# vme_conn.net
KiCad netlist of a schematic drawn in Altium Designer
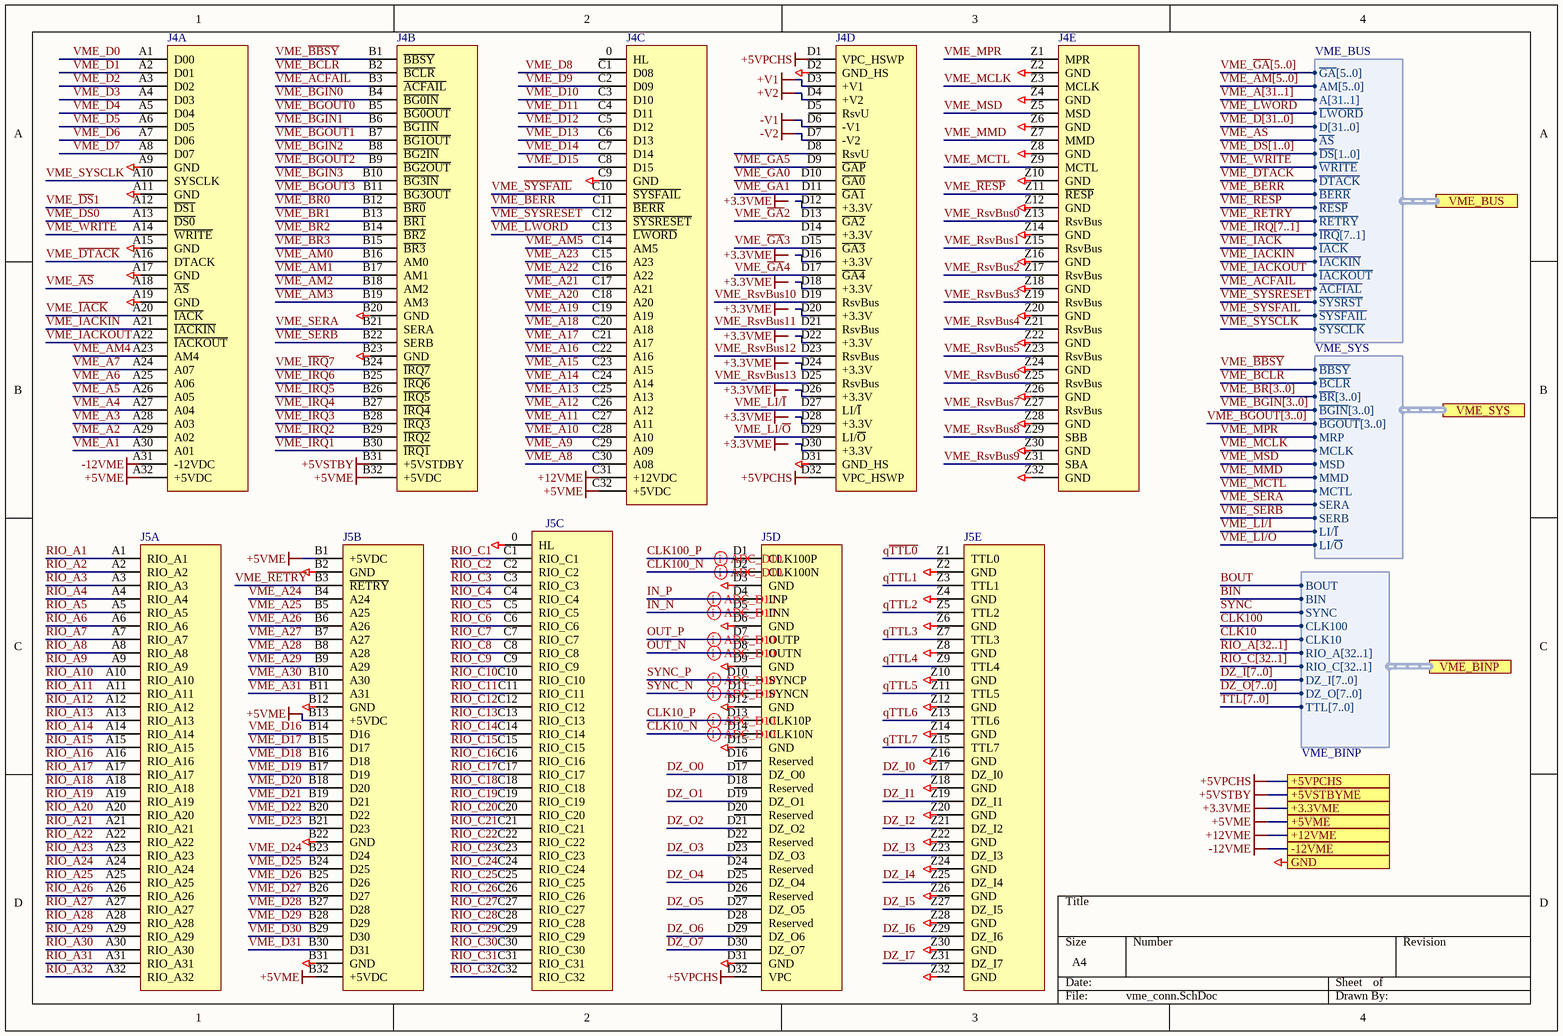
[diagram p0: vme_conn.SchDoc]

(export (version "E")
  (design (tool "Eeschema 10.0.6"))
  (components
    (comp (ref "J4")
      (value "DIN41612_160MR")
      (footprint "DIN41612-160P")
      (description "DIN 41612 5x32pin right angle male conector. VME P1 system connector")
      (libsource (lib "ConnLibScm") (part "VME_P1_160MR"))
    )
    (comp (ref "J5")
      (value "DIN41612_160MR")
      (footprint "DIN41612-160P")
      (description "DIN 41612 5x32pin right angle male conector. VME P2 system connector, VME BINP synch support")
      (libsource (lib "ConnLibScm") (part "VME_P2_160MR_BINP_V0"))
    )
  )
  (nets
    (net (code "13") (name "+5VME") (class "Default")
      (node (ref "J4") (pin "A32") (pinfunction "+5VDC_A32") (pintype "passive"))
      (node (ref "J4") (pin "B32") (pinfunction "+5VDC_B32") (pintype "passive"))
      (node (ref "J4") (pin "C32") (pinfunction "+5VDC_C32") (pintype "passive"))
      (node (ref "J5") (pin "B1") (pinfunction "+5VDC_B1") (pintype "passive"))
      (node (ref "J5") (pin "B13") (pinfunction "+5VDC_B13") (pintype "passive"))
      (node (ref "J5") (pin "B32") (pinfunction "+5VDC_B32") (pintype "passive"))
    )
    (net (code "14") (name "+5VPCHS") (class "Default")
      (node (ref "J4") (pin "D1") (pinfunction "VPC_HSWP_D1") (pintype "passive"))
      (node (ref "J4") (pin "D32") (pinfunction "VPC_HSWP_D32") (pintype "passive"))
      (node (ref "J5") (pin "D32") (pinfunction "VPC_D32") (pintype "passive"))
    )
    (net (code "15") (name "+5VSTBY") (class "Default")
      (node (ref "J4") (pin "B31") (pinfunction "+5VSTDBY_B31") (pintype "passive"))
    )
    (net (code "16") (name "+12VME") (class "Default")
      (node (ref "J4") (pin "C31") (pinfunction "+12VDC_C31") (pintype "passive"))
    )
    (net (code "17") (name "+V1") (class "Default")
      (node (ref "J4") (pin "D3") (pinfunction "+V1_D3") (pintype "passive"))
    )
    (net (code "18") (name "+V2") (class "Default")
      (node (ref "J4") (pin "D4") (pinfunction "+V2_D4") (pintype "passive"))
    )
    (net (code "19") (name "-12VME") (class "Default")
      (node (ref "J4") (pin "A31") (pinfunction "-12VDC_A31") (pintype "passive"))
    )
    (net (code "20") (name "-V1") (class "Default")
      (node (ref "J4") (pin "D6") (pinfunction "-V1_D6") (pintype "passive"))
    )
    (net (code "21") (name "-V2") (class "Default")
      (node (ref "J4") (pin "D7") (pinfunction "-V2_D7") (pintype "passive"))
    )
    (net (code "25") (name "/CLK10_N") (class "Default")
      (node (ref "J5") (pin "D14") (pinfunction "CLK10N_D14") (pintype "passive"))
    )
    (net (code "26") (name "/CLK10_P") (class "Default")
      (node (ref "J5") (pin "D13") (pinfunction "CLK10P_D13") (pintype "passive"))
    )
    (net (code "28") (name "/CLK100_N") (class "Default")
      (node (ref "J5") (pin "D2") (pinfunction "CLK100N_D2") (pintype "passive"))
    )
    (net (code "29") (name "/CLK100_P") (class "Default")
      (node (ref "J5") (pin "D1") (pinfunction "CLK100P_D1") (pintype "passive"))
    )
    (net (code "30") (name "/DZ_I0") (class "Default")
      (node (ref "J5") (pin "Z17") (pinfunction "DZ_I0_Z17") (pintype "passive"))
    )
    (net (code "31") (name "/DZ_I1") (class "Default")
      (node (ref "J5") (pin "Z19") (pinfunction "DZ_I1_Z19") (pintype "passive"))
    )
    (net (code "32") (name "/DZ_I2") (class "Default")
      (node (ref "J5") (pin "Z21") (pinfunction "DZ_I2_Z21") (pintype "passive"))
    )
    (net (code "33") (name "/DZ_I3") (class "Default")
      (node (ref "J5") (pin "Z23") (pinfunction "DZ_I3_Z23") (pintype "passive"))
    )
    (net (code "34") (name "/DZ_I4") (class "Default")
      (node (ref "J5") (pin "Z25") (pinfunction "DZ_I4_Z25") (pintype "passive"))
    )
    (net (code "35") (name "/DZ_I5") (class "Default")
      (node (ref "J5") (pin "Z27") (pinfunction "DZ_I5_Z27") (pintype "passive"))
    )
    (net (code "36") (name "/DZ_I6") (class "Default")
      (node (ref "J5") (pin "Z29") (pinfunction "DZ_I6_Z29") (pintype "passive"))
    )
    (net (code "37") (name "/DZ_I7") (class "Default")
      (node (ref "J5") (pin "Z31") (pinfunction "DZ_I7_Z31") (pintype "passive"))
    )
    (net (code "39") (name "/DZ_O0") (class "Default")
      (node (ref "J5") (pin "D17") (pinfunction "DZ_O0_D17") (pintype "passive"))
    )
    (net (code "40") (name "/DZ_O1") (class "Default")
      (node (ref "J5") (pin "D19") (pinfunction "DZ_O1_D19") (pintype "passive"))
    )
    (net (code "41") (name "/DZ_O2") (class "Default")
      (node (ref "J5") (pin "D21") (pinfunction "DZ_O2_D21") (pintype "passive"))
    )
    (net (code "42") (name "/DZ_O3") (class "Default")
      (node (ref "J5") (pin "D23") (pinfunction "DZ_O3_D23") (pintype "passive"))
    )
    (net (code "43") (name "/DZ_O4") (class "Default")
      (node (ref "J5") (pin "D25") (pinfunction "DZ_O4_D25") (pintype "passive"))
    )
    (net (code "44") (name "/DZ_O5") (class "Default")
      (node (ref "J5") (pin "D27") (pinfunction "DZ_O5_D27") (pintype "passive"))
    )
    (net (code "45") (name "/DZ_O6") (class "Default")
      (node (ref "J5") (pin "D29") (pinfunction "DZ_O6_D29") (pintype "passive"))
    )
    (net (code "46") (name "/DZ_O7") (class "Default")
      (node (ref "J5") (pin "D30") (pinfunction "DZ_O7_D30") (pintype "passive"))
    )
    (net (code "48") (name "/IN_N") (class "Default")
      (node (ref "J5") (pin "D5") (pinfunction "INN_D5") (pintype "passive"))
    )
    (net (code "49") (name "/IN_P") (class "Default")
      (node (ref "J5") (pin "D4") (pinfunction "INP_D4") (pintype "passive"))
    )
    (net (code "50") (name "/OUT_N") (class "Default")
      (node (ref "J5") (pin "D8") (pinfunction "OUTN_D8") (pintype "passive"))
    )
    (net (code "51") (name "/OUT_P") (class "Default")
      (node (ref "J5") (pin "D7") (pinfunction "OUTP_D7") (pintype "passive"))
    )
    (net (code "52") (name "/RIO_A1") (class "Default")
      (node (ref "J5") (pin "A1") (pinfunction "RIO_A1_A1") (pintype "passive"))
    )
    (net (code "53") (name "/RIO_A2") (class "Default")
      (node (ref "J5") (pin "A2") (pinfunction "RIO_A2_A2") (pintype "passive"))
    )
    (net (code "54") (name "/RIO_A3") (class "Default")
      (node (ref "J5") (pin "A3") (pinfunction "RIO_A3_A3") (pintype "passive"))
    )
    (net (code "55") (name "/RIO_A4") (class "Default")
      (node (ref "J5") (pin "A4") (pinfunction "RIO_A4_A4") (pintype "passive"))
    )
    (net (code "56") (name "/RIO_A5") (class "Default")
      (node (ref "J5") (pin "A5") (pinfunction "RIO_A5_A5") (pintype "passive"))
    )
    (net (code "57") (name "/RIO_A6") (class "Default")
      (node (ref "J5") (pin "A6") (pinfunction "RIO_A6_A6") (pintype "passive"))
    )
    (net (code "58") (name "/RIO_A7") (class "Default")
      (node (ref "J5") (pin "A7") (pinfunction "RIO_A7_A7") (pintype "passive"))
    )
    (net (code "59") (name "/RIO_A8") (class "Default")
      (node (ref "J5") (pin "A8") (pinfunction "RIO_A8_A8") (pintype "passive"))
    )
    (net (code "60") (name "/RIO_A9") (class "Default")
      (node (ref "J5") (pin "A9") (pinfunction "RIO_A9_A9") (pintype "passive"))
    )
    (net (code "61") (name "/RIO_A10") (class "Default")
      (node (ref "J5") (pin "A10") (pinfunction "RIO_A10_A10") (pintype "passive"))
    )
    (net (code "62") (name "/RIO_A11") (class "Default")
      (node (ref "J5") (pin "A11") (pinfunction "RIO_A11_A11") (pintype "passive"))
    )
    (net (code "63") (name "/RIO_A12") (class "Default")
      (node (ref "J5") (pin "A12") (pinfunction "RIO_A12_A12") (pintype "passive"))
    )
    (net (code "64") (name "/RIO_A13") (class "Default")
      (node (ref "J5") (pin "A13") (pinfunction "RIO_A13_A13") (pintype "passive"))
    )
    (net (code "65") (name "/RIO_A14") (class "Default")
      (node (ref "J5") (pin "A14") (pinfunction "RIO_A14_A14") (pintype "passive"))
    )
    (net (code "66") (name "/RIO_A15") (class "Default")
      (node (ref "J5") (pin "A15") (pinfunction "RIO_A15_A15") (pintype "passive"))
    )
    (net (code "67") (name "/RIO_A16") (class "Default")
      (node (ref "J5") (pin "A16") (pinfunction "RIO_A16_A16") (pintype "passive"))
    )
    (net (code "68") (name "/RIO_A17") (class "Default")
      (node (ref "J5") (pin "A17") (pinfunction "RIO_A17_A17") (pintype "passive"))
    )
    (net (code "69") (name "/RIO_A18") (class "Default")
      (node (ref "J5") (pin "A18") (pinfunction "RIO_A18_A18") (pintype "passive"))
    )
    (net (code "70") (name "/RIO_A19") (class "Default")
      (node (ref "J5") (pin "A19") (pinfunction "RIO_A19_A19") (pintype "passive"))
    )
    (net (code "71") (name "/RIO_A20") (class "Default")
      (node (ref "J5") (pin "A20") (pinfunction "RIO_A20_A20") (pintype "passive"))
    )
    (net (code "72") (name "/RIO_A21") (class "Default")
      (node (ref "J5") (pin "A21") (pinfunction "RIO_A21_A21") (pintype "passive"))
    )
    (net (code "73") (name "/RIO_A22") (class "Default")
      (node (ref "J5") (pin "A22") (pinfunction "RIO_A22_A22") (pintype "passive"))
    )
    (net (code "74") (name "/RIO_A23") (class "Default")
      (node (ref "J5") (pin "A23") (pinfunction "RIO_A23_A23") (pintype "passive"))
    )
    (net (code "75") (name "/RIO_A24") (class "Default")
      (node (ref "J5") (pin "A24") (pinfunction "RIO_A24_A24") (pintype "passive"))
    )
    (net (code "76") (name "/RIO_A25") (class "Default")
      (node (ref "J5") (pin "A25") (pinfunction "RIO_A25_A25") (pintype "passive"))
    )
    (net (code "77") (name "/RIO_A26") (class "Default")
      (node (ref "J5") (pin "A26") (pinfunction "RIO_A26_A26") (pintype "passive"))
    )
    (net (code "78") (name "/RIO_A27") (class "Default")
      (node (ref "J5") (pin "A27") (pinfunction "RIO_A27_A27") (pintype "passive"))
    )
    (net (code "79") (name "/RIO_A28") (class "Default")
      (node (ref "J5") (pin "A28") (pinfunction "RIO_A28_A28") (pintype "passive"))
    )
    (net (code "80") (name "/RIO_A29") (class "Default")
      (node (ref "J5") (pin "A29") (pinfunction "RIO_A29_A29") (pintype "passive"))
    )
    (net (code "81") (name "/RIO_A30") (class "Default")
      (node (ref "J5") (pin "A30") (pinfunction "RIO_A30_A30") (pintype "passive"))
    )
    (net (code "82") (name "/RIO_A31") (class "Default")
      (node (ref "J5") (pin "A31") (pinfunction "RIO_A31_A31") (pintype "passive"))
    )
    (net (code "83") (name "/RIO_A32") (class "Default")
      (node (ref "J5") (pin "A32") (pinfunction "RIO_A32_A32") (pintype "passive"))
    )
    (net (code "84") (name "/RIO_C1") (class "Default")
      (node (ref "J5") (pin "C1") (pinfunction "RIO_C1_C1") (pintype "passive"))
    )
    (net (code "85") (name "/RIO_C2") (class "Default")
      (node (ref "J5") (pin "C2") (pinfunction "RIO_C2_C2") (pintype "passive"))
    )
    (net (code "86") (name "/RIO_C3") (class "Default")
      (node (ref "J5") (pin "C3") (pinfunction "RIO_C3_C3") (pintype "passive"))
    )
    (net (code "87") (name "/RIO_C4") (class "Default")
      (node (ref "J5") (pin "C4") (pinfunction "RIO_C4_C4") (pintype "passive"))
    )
    (net (code "88") (name "/RIO_C5") (class "Default")
      (node (ref "J5") (pin "C5") (pinfunction "RIO_C5_C5") (pintype "passive"))
    )
    (net (code "89") (name "/RIO_C6") (class "Default")
      (node (ref "J5") (pin "C6") (pinfunction "RIO_C6_C6") (pintype "passive"))
    )
    (net (code "90") (name "/RIO_C7") (class "Default")
      (node (ref "J5") (pin "C7") (pinfunction "RIO_C7_C7") (pintype "passive"))
    )
    (net (code "91") (name "/RIO_C8") (class "Default")
      (node (ref "J5") (pin "C8") (pinfunction "RIO_C8_C8") (pintype "passive"))
    )
    (net (code "92") (name "/RIO_C9") (class "Default")
      (node (ref "J5") (pin "C9") (pinfunction "RIO_C9_C9") (pintype "passive"))
    )
    (net (code "93") (name "/RIO_C10") (class "Default")
      (node (ref "J5") (pin "C10") (pinfunction "RIO_C10_C10") (pintype "passive"))
    )
    (net (code "94") (name "/RIO_C11") (class "Default")
      (node (ref "J5") (pin "C11") (pinfunction "RIO_C11_C11") (pintype "passive"))
    )
    (net (code "95") (name "/RIO_C12") (class "Default")
      (node (ref "J5") (pin "C12") (pinfunction "RIO_C12_C12") (pintype "passive"))
    )
    (net (code "96") (name "/RIO_C13") (class "Default")
      (node (ref "J5") (pin "C13") (pinfunction "RIO_C13_C13") (pintype "passive"))
    )
    (net (code "97") (name "/RIO_C14") (class "Default")
      (node (ref "J5") (pin "C14") (pinfunction "RIO_C14_C14") (pintype "passive"))
    )
    (net (code "98") (name "/RIO_C15") (class "Default")
      (node (ref "J5") (pin "C15") (pinfunction "RIO_C15_C15") (pintype "passive"))
    )
    (net (code "99") (name "/RIO_C16") (class "Default")
      (node (ref "J5") (pin "C16") (pinfunction "RIO_C16_C16") (pintype "passive"))
    )
    (net (code "100") (name "/RIO_C17") (class "Default")
      (node (ref "J5") (pin "C17") (pinfunction "RIO_C17_C17") (pintype "passive"))
    )
    (net (code "101") (name "/RIO_C18") (class "Default")
      (node (ref "J5") (pin "C18") (pinfunction "RIO_C18_C18") (pintype "passive"))
    )
    (net (code "102") (name "/RIO_C19") (class "Default")
      (node (ref "J5") (pin "C19") (pinfunction "RIO_C19_C19") (pintype "passive"))
    )
    (net (code "103") (name "/RIO_C20") (class "Default")
      (node (ref "J5") (pin "C20") (pinfunction "RIO_C20_C20") (pintype "passive"))
    )
    (net (code "104") (name "/RIO_C21") (class "Default")
      (node (ref "J5") (pin "C21") (pinfunction "RIO_C21_C21") (pintype "passive"))
    )
    (net (code "105") (name "/RIO_C22") (class "Default")
      (node (ref "J5") (pin "C22") (pinfunction "RIO_C22_C22") (pintype "passive"))
    )
    (net (code "106") (name "/RIO_C23") (class "Default")
      (node (ref "J5") (pin "C23") (pinfunction "RIO_C23_C23") (pintype "passive"))
    )
    (net (code "107") (name "/RIO_C24") (class "Default")
      (node (ref "J5") (pin "C24") (pinfunction "RIO_C24_C24") (pintype "passive"))
    )
    (net (code "108") (name "/RIO_C25") (class "Default")
      (node (ref "J5") (pin "C25") (pinfunction "RIO_C25_C25") (pintype "passive"))
    )
    (net (code "109") (name "/RIO_C26") (class "Default")
      (node (ref "J5") (pin "C26") (pinfunction "RIO_C26_C26") (pintype "passive"))
    )
    (net (code "110") (name "/RIO_C27") (class "Default")
      (node (ref "J5") (pin "C27") (pinfunction "RIO_C27_C27") (pintype "passive"))
    )
    (net (code "111") (name "/RIO_C28") (class "Default")
      (node (ref "J5") (pin "C28") (pinfunction "RIO_C28_C28") (pintype "passive"))
    )
    (net (code "112") (name "/RIO_C29") (class "Default")
      (node (ref "J5") (pin "C29") (pinfunction "RIO_C29_C29") (pintype "passive"))
    )
    (net (code "113") (name "/RIO_C30") (class "Default")
      (node (ref "J5") (pin "C30") (pinfunction "RIO_C30_C30") (pintype "passive"))
    )
    (net (code "114") (name "/RIO_C31") (class "Default")
      (node (ref "J5") (pin "C31") (pinfunction "RIO_C31_C31") (pintype "passive"))
    )
    (net (code "115") (name "/RIO_C32") (class "Default")
      (node (ref "J5") (pin "C32") (pinfunction "RIO_C32_C32") (pintype "passive"))
    )
    (net (code "118") (name "/SYNC_N") (class "Default")
      (node (ref "J5") (pin "D11") (pinfunction "SYNCN_D11") (pintype "passive"))
    )
    (net (code "119") (name "/SYNC_P") (class "Default")
      (node (ref "J5") (pin "D10") (pinfunction "SYNCP_D10") (pintype "passive"))
    )
    (net (code "121") (name "/VME_A1") (class "Default")
      (node (ref "J4") (pin "A30") (pinfunction "A01_A30") (pintype "passive"))
    )
    (net (code "122") (name "/VME_A2") (class "Default")
      (node (ref "J4") (pin "A29") (pinfunction "A02_A29") (pintype "passive"))
    )
    (net (code "123") (name "/VME_A3") (class "Default")
      (node (ref "J4") (pin "A28") (pinfunction "A03_A28") (pintype "passive"))
    )
    (net (code "124") (name "/VME_A4") (class "Default")
      (node (ref "J4") (pin "A27") (pinfunction "A04_A27") (pintype "passive"))
    )
    (net (code "125") (name "/VME_A5") (class "Default")
      (node (ref "J4") (pin "A26") (pinfunction "A05_A26") (pintype "passive"))
    )
    (net (code "126") (name "/VME_A6") (class "Default")
      (node (ref "J4") (pin "A25") (pinfunction "A06_A25") (pintype "passive"))
    )
    (net (code "127") (name "/VME_A7") (class "Default")
      (node (ref "J4") (pin "A24") (pinfunction "A07_A24") (pintype "passive"))
    )
    (net (code "128") (name "/VME_A8") (class "Default")
      (node (ref "J4") (pin "C30") (pinfunction "A08_C30") (pintype "passive"))
    )
    (net (code "129") (name "/VME_A9") (class "Default")
      (node (ref "J4") (pin "C29") (pinfunction "A09_C29") (pintype "passive"))
    )
    (net (code "130") (name "/VME_A10") (class "Default")
      (node (ref "J4") (pin "C28") (pinfunction "A10_C28") (pintype "passive"))
    )
    (net (code "131") (name "/VME_A11") (class "Default")
      (node (ref "J4") (pin "C27") (pinfunction "A11_C27") (pintype "passive"))
    )
    (net (code "132") (name "/VME_A12") (class "Default")
      (node (ref "J4") (pin "C26") (pinfunction "A12_C26") (pintype "passive"))
    )
    (net (code "133") (name "/VME_A13") (class "Default")
      (node (ref "J4") (pin "C25") (pinfunction "A13_C25") (pintype "passive"))
    )
    (net (code "134") (name "/VME_A14") (class "Default")
      (node (ref "J4") (pin "C24") (pinfunction "A14_C24") (pintype "passive"))
    )
    (net (code "135") (name "/VME_A15") (class "Default")
      (node (ref "J4") (pin "C23") (pinfunction "A15_C23") (pintype "passive"))
    )
    (net (code "136") (name "/VME_A16") (class "Default")
      (node (ref "J4") (pin "C22") (pinfunction "A16_C22") (pintype "passive"))
    )
    (net (code "137") (name "/VME_A17") (class "Default")
      (node (ref "J4") (pin "C21") (pinfunction "A17_C21") (pintype "passive"))
    )
    (net (code "138") (name "/VME_A18") (class "Default")
      (node (ref "J4") (pin "C20") (pinfunction "A18_C20") (pintype "passive"))
    )
    (net (code "139") (name "/VME_A19") (class "Default")
      (node (ref "J4") (pin "C19") (pinfunction "A19_C19") (pintype "passive"))
    )
    (net (code "140") (name "/VME_A20") (class "Default")
      (node (ref "J4") (pin "C18") (pinfunction "A20_C18") (pintype "passive"))
    )
    (net (code "141") (name "/VME_A21") (class "Default")
      (node (ref "J4") (pin "C17") (pinfunction "A21_C17") (pintype "passive"))
    )
    (net (code "142") (name "/VME_A22") (class "Default")
      (node (ref "J4") (pin "C16") (pinfunction "A22_C16") (pintype "passive"))
    )
    (net (code "143") (name "/VME_A23") (class "Default")
      (node (ref "J4") (pin "C15") (pinfunction "A23_C15") (pintype "passive"))
    )
    (net (code "144") (name "/VME_A24") (class "Default")
      (node (ref "J5") (pin "B4") (pinfunction "A24_B4") (pintype "passive"))
    )
    (net (code "145") (name "/VME_A25") (class "Default")
      (node (ref "J5") (pin "B5") (pinfunction "A25_B5") (pintype "passive"))
    )
    (net (code "146") (name "/VME_A26") (class "Default")
      (node (ref "J5") (pin "B6") (pinfunction "A26_B6") (pintype "passive"))
    )
    (net (code "147") (name "/VME_A27") (class "Default")
      (node (ref "J5") (pin "B7") (pinfunction "A27_B7") (pintype "passive"))
    )
    (net (code "148") (name "/VME_A28") (class "Default")
      (node (ref "J5") (pin "B8") (pinfunction "A28_B8") (pintype "passive"))
    )
    (net (code "149") (name "/VME_A29") (class "Default")
      (node (ref "J5") (pin "B9") (pinfunction "A29_B9") (pintype "passive"))
    )
    (net (code "150") (name "/VME_A30") (class "Default")
      (node (ref "J5") (pin "B10") (pinfunction "A30_B10") (pintype "passive"))
    )
    (net (code "151") (name "/VME_A31") (class "Default")
      (node (ref "J5") (pin "B11") (pinfunction "A31_B11") (pintype "passive"))
    )
    (net (code "152") (name "/VME_AM0") (class "Default")
      (node (ref "J4") (pin "B16") (pinfunction "AM0_B16") (pintype "passive"))
    )
    (net (code "153") (name "/VME_AM1") (class "Default")
      (node (ref "J4") (pin "B17") (pinfunction "AM1_B17") (pintype "passive"))
    )
    (net (code "154") (name "/VME_AM2") (class "Default")
      (node (ref "J4") (pin "B18") (pinfunction "AM2_B18") (pintype "passive"))
    )
    (net (code "155") (name "/VME_AM3") (class "Default")
      (node (ref "J4") (pin "B19") (pinfunction "AM3_B19") (pintype "passive"))
    )
    (net (code "156") (name "/VME_AM4") (class "Default")
      (node (ref "J4") (pin "A23") (pinfunction "AM4_A23") (pintype "passive"))
    )
    (net (code "157") (name "/VME_AM5") (class "Default")
      (node (ref "J4") (pin "C14") (pinfunction "AM5_C14") (pintype "passive"))
    )
    (net (code "162") (name "/VME_D0") (class "Default")
      (node (ref "J4") (pin "A1") (pinfunction "D00_A1") (pintype "passive"))
    )
    (net (code "163") (name "/VME_D1") (class "Default")
      (node (ref "J4") (pin "A2") (pinfunction "D01_A2") (pintype "passive"))
    )
    (net (code "164") (name "/VME_D2") (class "Default")
      (node (ref "J4") (pin "A3") (pinfunction "D02_A3") (pintype "passive"))
    )
    (net (code "165") (name "/VME_D3") (class "Default")
      (node (ref "J4") (pin "A4") (pinfunction "D03_A4") (pintype "passive"))
    )
    (net (code "166") (name "/VME_D4") (class "Default")
      (node (ref "J4") (pin "A5") (pinfunction "D04_A5") (pintype "passive"))
    )
    (net (code "167") (name "/VME_D5") (class "Default")
      (node (ref "J4") (pin "A6") (pinfunction "D05_A6") (pintype "passive"))
    )
    (net (code "168") (name "/VME_D6") (class "Default")
      (node (ref "J4") (pin "A7") (pinfunction "D06_A7") (pintype "passive"))
    )
    (net (code "169") (name "/VME_D7") (class "Default")
      (node (ref "J4") (pin "A8") (pinfunction "D07_A8") (pintype "passive"))
    )
    (net (code "170") (name "/VME_D8") (class "Default")
      (node (ref "J4") (pin "C1") (pinfunction "D08_C1") (pintype "passive"))
    )
    (net (code "171") (name "/VME_D9") (class "Default")
      (node (ref "J4") (pin "C2") (pinfunction "D09_C2") (pintype "passive"))
    )
    (net (code "172") (name "/VME_D10") (class "Default")
      (node (ref "J4") (pin "C3") (pinfunction "D10_C3") (pintype "passive"))
    )
    (net (code "173") (name "/VME_D11") (class "Default")
      (node (ref "J4") (pin "C4") (pinfunction "D11_C4") (pintype "passive"))
    )
    (net (code "174") (name "/VME_D12") (class "Default")
      (node (ref "J4") (pin "C5") (pinfunction "D12_C5") (pintype "passive"))
    )
    (net (code "175") (name "/VME_D13") (class "Default")
      (node (ref "J4") (pin "C6") (pinfunction "D13_C6") (pintype "passive"))
    )
    (net (code "176") (name "/VME_D14") (class "Default")
      (node (ref "J4") (pin "C7") (pinfunction "D14_C7") (pintype "passive"))
    )
    (net (code "177") (name "/VME_D15") (class "Default")
      (node (ref "J4") (pin "C8") (pinfunction "D15_C8") (pintype "passive"))
    )
    (net (code "178") (name "/VME_D16") (class "Default")
      (node (ref "J5") (pin "B14") (pinfunction "D16_B14") (pintype "passive"))
    )
    (net (code "179") (name "/VME_D17") (class "Default")
      (node (ref "J5") (pin "B15") (pinfunction "D17_B15") (pintype "passive"))
    )
    (net (code "180") (name "/VME_D18") (class "Default")
      (node (ref "J5") (pin "B16") (pinfunction "D18_B16") (pintype "passive"))
    )
    (net (code "181") (name "/VME_D19") (class "Default")
      (node (ref "J5") (pin "B17") (pinfunction "D19_B17") (pintype "passive"))
    )
    (net (code "182") (name "/VME_D20") (class "Default")
      (node (ref "J5") (pin "B18") (pinfunction "D20_B18") (pintype "passive"))
    )
    (net (code "183") (name "/VME_D21") (class "Default")
      (node (ref "J5") (pin "B19") (pinfunction "D21_B19") (pintype "passive"))
    )
    (net (code "184") (name "/VME_D22") (class "Default")
      (node (ref "J5") (pin "B20") (pinfunction "D22_B20") (pintype "passive"))
    )
    (net (code "185") (name "/VME_D23") (class "Default")
      (node (ref "J5") (pin "B21") (pinfunction "D23_B21") (pintype "passive"))
    )
    (net (code "186") (name "/VME_D24") (class "Default")
      (node (ref "J5") (pin "B23") (pinfunction "D24_B23") (pintype "passive"))
    )
    (net (code "187") (name "/VME_D25") (class "Default")
      (node (ref "J5") (pin "B24") (pinfunction "D25_B24") (pintype "passive"))
    )
    (net (code "188") (name "/VME_D26") (class "Default")
      (node (ref "J5") (pin "B25") (pinfunction "D26_B25") (pintype "passive"))
    )
    (net (code "189") (name "/VME_D27") (class "Default")
      (node (ref "J5") (pin "B26") (pinfunction "D27_B26") (pintype "passive"))
    )
    (net (code "190") (name "/VME_D28") (class "Default")
      (node (ref "J5") (pin "B27") (pinfunction "D28_B27") (pintype "passive"))
    )
    (net (code "191") (name "/VME_D29") (class "Default")
      (node (ref "J5") (pin "B28") (pinfunction "D29_B28") (pintype "passive"))
    )
    (net (code "192") (name "/VME_D30") (class "Default")
      (node (ref "J5") (pin "B29") (pinfunction "D30_B29") (pintype "passive"))
    )
    (net (code "193") (name "/VME_D31") (class "Default")
      (node (ref "J5") (pin "B30") (pinfunction "D31_B30") (pintype "passive"))
    )
    (net (code "195") (name "/VME_LI{slash}~{I}") (class "Default")
      (node (ref "J4") (pin "D27") (pinfunction "LI/~{I}_D27") (pintype "passive"))
    )
    (net (code "196") (name "/VME_LI{slash}~{O}") (class "Default")
      (node (ref "J4") (pin "D29") (pinfunction "LI/~{O}_D29") (pintype "passive"))
    )
    (net (code "197") (name "/VME_MCLK") (class "Default")
      (node (ref "J4") (pin "Z3") (pinfunction "MCLK_Z3") (pintype "passive"))
    )
    (net (code "198") (name "/VME_MCTL") (class "Default")
      (node (ref "J4") (pin "Z9") (pinfunction "MCTL_Z9") (pintype "passive"))
    )
    (net (code "199") (name "/VME_MMD") (class "Default")
      (node (ref "J4") (pin "Z7") (pinfunction "MMD_Z7") (pintype "passive"))
    )
    (net (code "200") (name "/VME_MPR") (class "Default")
      (node (ref "J4") (pin "Z1") (pinfunction "MPR_Z1") (pintype "passive"))
    )
    (net (code "201") (name "/VME_MSD") (class "Default")
      (node (ref "J4") (pin "Z5") (pinfunction "MSD_Z5") (pintype "passive"))
    )
    (net (code "202") (name "/VME_RsvBus0") (class "Default")
      (node (ref "J4") (pin "Z13") (pinfunction "RsvBus_Z13") (pintype "passive"))
    )
    (net (code "203") (name "/VME_RsvBus1") (class "Default")
      (node (ref "J4") (pin "Z15") (pinfunction "RsvBus_Z15") (pintype "passive"))
    )
    (net (code "204") (name "/VME_RsvBus2") (class "Default")
      (node (ref "J4") (pin "Z17") (pinfunction "RsvBus_Z17") (pintype "passive"))
    )
    (net (code "205") (name "/VME_RsvBus3") (class "Default")
      (node (ref "J4") (pin "Z19") (pinfunction "RsvBus_Z19") (pintype "passive"))
    )
    (net (code "206") (name "/VME_RsvBus4") (class "Default")
      (node (ref "J4") (pin "Z21") (pinfunction "RsvBus_Z21") (pintype "passive"))
    )
    (net (code "207") (name "/VME_RsvBus5") (class "Default")
      (node (ref "J4") (pin "Z23") (pinfunction "RsvBus_Z23") (pintype "passive"))
    )
    (net (code "208") (name "/VME_RsvBus6") (class "Default")
      (node (ref "J4") (pin "Z25") (pinfunction "RsvBus_Z25") (pintype "passive"))
    )
    (net (code "209") (name "/VME_RsvBus7") (class "Default")
      (node (ref "J4") (pin "Z27") (pinfunction "RsvBus_Z27") (pintype "passive"))
    )
    (net (code "210") (name "/VME_RsvBus8") (class "Default")
      (node (ref "J4") (pin "Z29") (pinfunction "SBB_Z29") (pintype "passive"))
    )
    (net (code "211") (name "/VME_RsvBus9") (class "Default")
      (node (ref "J4") (pin "Z31") (pinfunction "SBA_Z31") (pintype "passive"))
    )
    (net (code "212") (name "/VME_RsvBus10") (class "Default")
      (node (ref "J4") (pin "D19") (pinfunction "RsvBus_D19") (pintype "passive"))
    )
    (net (code "213") (name "/VME_RsvBus11") (class "Default")
      (node (ref "J4") (pin "D21") (pinfunction "RsvBus_D21") (pintype "passive"))
    )
    (net (code "214") (name "/VME_RsvBus12") (class "Default")
      (node (ref "J4") (pin "D23") (pinfunction "RsvBus_D23") (pintype "passive"))
    )
    (net (code "215") (name "/VME_RsvBus13") (class "Default")
      (node (ref "J4") (pin "D25") (pinfunction "RsvBus_D25") (pintype "passive"))
    )
    (net (code "216") (name "/VME_SERA") (class "Default")
      (node (ref "J4") (pin "B21") (pinfunction "SERA_B21") (pintype "passive"))
    )
    (net (code "217") (name "/VME_SERB") (class "Default")
      (node (ref "J4") (pin "B22") (pinfunction "SERB_B22") (pintype "passive"))
    )
    (net (code "218") (name "/VME_SYSCLK") (class "Default")
      (node (ref "J4") (pin "A10") (pinfunction "SYSCLK_A10") (pintype "passive"))
    )
    (net (code "219") (name "/VME_~{ACFAIL}") (class "Default")
      (node (ref "J4") (pin "B3") (pinfunction "~{ACFAIL}_B3") (pintype "passive"))
    )
    (net (code "220") (name "/VME_~{AS}") (class "Default")
      (node (ref "J4") (pin "A18") (pinfunction "~{AS}_A18") (pintype "passive"))
    )
    (net (code "221") (name "/VME_~{BBSY}") (class "Default")
      (node (ref "J4") (pin "B1") (pinfunction "~{BBSY}_B1") (pintype "passive"))
    )
    (net (code "222") (name "/VME_~{BCLR}") (class "Default")
      (node (ref "J4") (pin "B2") (pinfunction "~{BCLR}_B2") (pintype "passive"))
    )
    (net (code "223") (name "/VME_~{BERR}") (class "Default")
      (node (ref "J4") (pin "C11") (pinfunction "~{BERR}_C11") (pintype "passive"))
    )
    (net (code "224") (name "/VME_~{BGIN}0") (class "Default")
      (node (ref "J4") (pin "B4") (pinfunction "~{BG0IN}_B4") (pintype "passive"))
    )
    (net (code "225") (name "/VME_~{BGIN}1") (class "Default")
      (node (ref "J4") (pin "B6") (pinfunction "~{BG1IN}_B6") (pintype "passive"))
    )
    (net (code "226") (name "/VME_~{BGIN}2") (class "Default")
      (node (ref "J4") (pin "B8") (pinfunction "~{BG2IN}_B8") (pintype "passive"))
    )
    (net (code "227") (name "/VME_~{BGIN}3") (class "Default")
      (node (ref "J4") (pin "B10") (pinfunction "~{BG3IN}_B10") (pintype "passive"))
    )
    (net (code "229") (name "/VME_~{BGOUT}0") (class "Default")
      (node (ref "J4") (pin "B5") (pinfunction "~{BG0OUT}_B5") (pintype "passive"))
    )
    (net (code "230") (name "/VME_~{BGOUT}1") (class "Default")
      (node (ref "J4") (pin "B7") (pinfunction "~{BG1OUT}_B7") (pintype "passive"))
    )
    (net (code "231") (name "/VME_~{BGOUT}2") (class "Default")
      (node (ref "J4") (pin "B9") (pinfunction "~{BG2OUT}_B9") (pintype "passive"))
    )
    (net (code "232") (name "/VME_~{BGOUT}3") (class "Default")
      (node (ref "J4") (pin "B11") (pinfunction "~{BG3OUT}_B11") (pintype "passive"))
    )
    (net (code "234") (name "/VME_~{BR}0") (class "Default")
      (node (ref "J4") (pin "B12") (pinfunction "~{BR0}_B12") (pintype "passive"))
    )
    (net (code "235") (name "/VME_~{BR}1") (class "Default")
      (node (ref "J4") (pin "B13") (pinfunction "~{BR1}_B13") (pintype "passive"))
    )
    (net (code "236") (name "/VME_~{BR}2") (class "Default")
      (node (ref "J4") (pin "B14") (pinfunction "~{BR2}_B14") (pintype "passive"))
    )
    (net (code "237") (name "/VME_~{BR}3") (class "Default")
      (node (ref "J4") (pin "B15") (pinfunction "~{BR3}_B15") (pintype "passive"))
    )
    (net (code "239") (name "/VME_~{DS}0") (class "Default")
      (node (ref "J4") (pin "A13") (pinfunction "~{DS0}_A13") (pintype "passive"))
    )
    (net (code "240") (name "/VME_~{DS}1") (class "Default")
      (node (ref "J4") (pin "A12") (pinfunction "~{DS1}_A12") (pintype "passive"))
    )
    (net (code "242") (name "/VME_~{DTACK}") (class "Default")
      (node (ref "J4") (pin "A16") (pinfunction "DTACK_A16") (pintype "passive"))
    )
    (net (code "243") (name "/VME_~{GA}0") (class "Default")
      (node (ref "J4") (pin "D10") (pinfunction "~{GA0}_D10") (pintype "passive"))
    )
    (net (code "244") (name "/VME_~{GA}1") (class "Default")
      (node (ref "J4") (pin "D11") (pinfunction "~{GA1}_D11") (pintype "passive"))
    )
    (net (code "245") (name "/VME_~{GA}2") (class "Default")
      (node (ref "J4") (pin "D13") (pinfunction "~{GA2}_D13") (pintype "passive"))
    )
    (net (code "246") (name "/VME_~{GA}3") (class "Default")
      (node (ref "J4") (pin "D15") (pinfunction "~{GA3}_D15") (pintype "passive"))
    )
    (net (code "247") (name "/VME_~{GA}4") (class "Default")
      (node (ref "J4") (pin "D17") (pinfunction "~{GA4}_D17") (pintype "passive"))
    )
    (net (code "248") (name "/VME_~{GA}5") (class "Default")
      (node (ref "J4") (pin "D9") (pinfunction "~{GAP}_D9") (pintype "passive"))
    )
    (net (code "249") (name "/VME_~{IACKIN}") (class "Default")
      (node (ref "J4") (pin "A21") (pinfunction "~{IACKIN}_A21") (pintype "passive"))
    )
    (net (code "250") (name "/VME_~{IACKOUT}") (class "Default")
      (node (ref "J4") (pin "A22") (pinfunction "~{IACKOUT}_A22") (pintype "passive"))
    )
    (net (code "251") (name "/VME_~{IACK}") (class "Default")
      (node (ref "J4") (pin "A20") (pinfunction "~{IACK}_A20") (pintype "passive"))
    )
    (net (code "252") (name "/VME_~{IRQ}1") (class "Default")
      (node (ref "J4") (pin "B30") (pinfunction "~{IRQ1}_B30") (pintype "passive"))
    )
    (net (code "253") (name "/VME_~{IRQ}2") (class "Default")
      (node (ref "J4") (pin "B29") (pinfunction "~{IRQ2}_B29") (pintype "passive"))
    )
    (net (code "254") (name "/VME_~{IRQ}3") (class "Default")
      (node (ref "J4") (pin "B28") (pinfunction "~{IRQ3}_B28") (pintype "passive"))
    )
    (net (code "255") (name "/VME_~{IRQ}4") (class "Default")
      (node (ref "J4") (pin "B27") (pinfunction "~{IRQ4}_B27") (pintype "passive"))
    )
    (net (code "256") (name "/VME_~{IRQ}5") (class "Default")
      (node (ref "J4") (pin "B26") (pinfunction "~{IRQ5}_B26") (pintype "passive"))
    )
    (net (code "257") (name "/VME_~{IRQ}6") (class "Default")
      (node (ref "J4") (pin "B25") (pinfunction "~{IRQ6}_B25") (pintype "passive"))
    )
    (net (code "258") (name "/VME_~{IRQ}7") (class "Default")
      (node (ref "J4") (pin "B24") (pinfunction "~{IRQ7}_B24") (pintype "passive"))
    )
    (net (code "260") (name "/VME_~{LWORD}") (class "Default")
      (node (ref "J4") (pin "C13") (pinfunction "~{LWORD}_C13") (pintype "passive"))
    )
    (net (code "261") (name "/VME_~{RESP}") (class "Default")
      (node (ref "J4") (pin "Z11") (pinfunction "~{RESP}_Z11") (pintype "passive"))
    )
    (net (code "262") (name "/VME_~{RETRY}") (class "Default")
      (node (ref "J5") (pin "B3") (pinfunction "~{RETRY}_B3") (pintype "passive"))
    )
    (net (code "263") (name "/VME_~{SYSFAIL}") (class "Default")
      (node (ref "J4") (pin "C10") (pinfunction "~{SYSFAIL}_C10") (pintype "passive"))
    )
    (net (code "264") (name "/VME_~{SYSRESET}") (class "Default")
      (node (ref "J4") (pin "C12") (pinfunction "~{SYSRESET}_C12") (pintype "passive"))
    )
    (net (code "265") (name "/VME_~{WRITE}") (class "Default")
      (node (ref "J4") (pin "A14") (pinfunction "~{WRITE}_A14") (pintype "passive"))
    )
    (net (code "266") (name "/qTTL1") (class "Default")
      (node (ref "J5") (pin "Z3") (pinfunction "TTL1_Z3") (pintype "passive"))
    )
    (net (code "267") (name "/qTTL2") (class "Default")
      (node (ref "J5") (pin "Z5") (pinfunction "TTL2_Z5") (pintype "passive"))
    )
    (net (code "268") (name "/qTTL3") (class "Default")
      (node (ref "J5") (pin "Z7") (pinfunction "TTL3_Z7") (pintype "passive"))
    )
    (net (code "269") (name "/qTTL4") (class "Default")
      (node (ref "J5") (pin "Z9") (pinfunction "TTL4_Z9") (pintype "passive"))
    )
    (net (code "270") (name "/qTTL5") (class "Default")
      (node (ref "J5") (pin "Z11") (pinfunction "TTL5_Z11") (pintype "passive"))
    )
    (net (code "271") (name "/qTTL6") (class "Default")
      (node (ref "J5") (pin "Z13") (pinfunction "TTL6_Z13") (pintype "passive"))
    )
    (net (code "272") (name "/qTTL7") (class "Default")
      (node (ref "J5") (pin "Z15") (pinfunction "TTL7_Z15") (pintype "passive"))
    )
    (net (code "273") (name "/q~{TTL0}") (class "Default")
      (node (ref "J5") (pin "Z1") (pinfunction "TTL0_Z1") (pintype "passive"))
    )
    (net (code "276") (name "GND") (class "Default")
      (node (ref "J4") (pin "A11") (pinfunction "GND_A11") (pintype "passive"))
      (node (ref "J4") (pin "A15") (pinfunction "GND_A15") (pintype "passive"))
      (node (ref "J4") (pin "A17") (pinfunction "GND_A17") (pintype "passive"))
      (node (ref "J4") (pin "A19") (pinfunction "GND_A19") (pintype "passive"))
      (node (ref "J4") (pin "A9") (pinfunction "GND_A9") (pintype "passive"))
      (node (ref "J4") (pin "B20") (pinfunction "GND_B20") (pintype "passive"))
      (node (ref "J4") (pin "B23") (pinfunction "GND_B23") (pintype "passive"))
      (node (ref "J4") (pin "C9") (pinfunction "GND_C9") (pintype "passive"))
      (node (ref "J4") (pin "D2") (pinfunction "GND_HS_D2") (pintype "passive"))
      (node (ref "J4") (pin "D31") (pinfunction "GND_HS_D31") (pintype "passive"))
      (node (ref "J4") (pin "Z10") (pinfunction "GND_Z10") (pintype "passive"))
      (node (ref "J4") (pin "Z12") (pinfunction "GND_Z12") (pintype "passive"))
      (node (ref "J4") (pin "Z14") (pinfunction "GND_Z14") (pintype "passive"))
      (node (ref "J4") (pin "Z16") (pinfunction "GND_Z16") (pintype "passive"))
      (node (ref "J4") (pin "Z18") (pinfunction "GND_Z18") (pintype "passive"))
      (node (ref "J4") (pin "Z2") (pinfunction "GND_Z2") (pintype "passive"))
      (node (ref "J4") (pin "Z20") (pinfunction "GND_Z20") (pintype "passive"))
      (node (ref "J4") (pin "Z22") (pinfunction "GND_Z22") (pintype "passive"))
      (node (ref "J4") (pin "Z24") (pinfunction "GND_Z24") (pintype "passive"))
      (node (ref "J4") (pin "Z26") (pinfunction "GND_Z26") (pintype "passive"))
      (node (ref "J4") (pin "Z28") (pinfunction "GND_Z28") (pintype "passive"))
      (node (ref "J4") (pin "Z30") (pinfunction "GND_Z30") (pintype "passive"))
      (node (ref "J4") (pin "Z32") (pinfunction "GND_Z32") (pintype "passive"))
      (node (ref "J4") (pin "Z4") (pinfunction "GND_Z4") (pintype "passive"))
      (node (ref "J4") (pin "Z6") (pinfunction "GND_Z6") (pintype "passive"))
      (node (ref "J4") (pin "Z8") (pinfunction "GND_Z8") (pintype "passive"))
      (node (ref "J5") (pin "0") (pinfunction "HL_0") (pintype "passive"))
      (node (ref "J5") (pin "B12") (pinfunction "GND_B12") (pintype "passive"))
      (node (ref "J5") (pin "B2") (pinfunction "GND_B2") (pintype "passive"))
      (node (ref "J5") (pin "B22") (pinfunction "GND_B22") (pintype "passive"))
      (node (ref "J5") (pin "B31") (pinfunction "GND_B31") (pintype "passive"))
      (node (ref "J5") (pin "D12") (pinfunction "GND_D12") (pintype "passive"))
      (node (ref "J5") (pin "D15") (pinfunction "GND_D15") (pintype "passive"))
      (node (ref "J5") (pin "D3") (pinfunction "GND_D3") (pintype "passive"))
      (node (ref "J5") (pin "D31") (pinfunction "GND_D31") (pintype "passive"))
      (node (ref "J5") (pin "D6") (pinfunction "GND_D6") (pintype "passive"))
      (node (ref "J5") (pin "D9") (pinfunction "GND_D9") (pintype "passive"))
      (node (ref "J5") (pin "Z10") (pinfunction "GND_Z10") (pintype "passive"))
      (node (ref "J5") (pin "Z12") (pinfunction "GND_Z12") (pintype "passive"))
      (node (ref "J5") (pin "Z14") (pinfunction "GND_Z14") (pintype "passive"))
      (node (ref "J5") (pin "Z16") (pinfunction "GND_Z16") (pintype "passive"))
      (node (ref "J5") (pin "Z18") (pinfunction "GND_Z18") (pintype "passive"))
      (node (ref "J5") (pin "Z2") (pinfunction "GND_Z2") (pintype "passive"))
      (node (ref "J5") (pin "Z20") (pinfunction "GND_Z20") (pintype "passive"))
      (node (ref "J5") (pin "Z22") (pinfunction "GND_Z22") (pintype "passive"))
      (node (ref "J5") (pin "Z24") (pinfunction "GND_Z24") (pintype "passive"))
      (node (ref "J5") (pin "Z26") (pinfunction "GND_Z26") (pintype "passive"))
      (node (ref "J5") (pin "Z28") (pinfunction "GND_Z28") (pintype "passive"))
      (node (ref "J5") (pin "Z30") (pinfunction "GND_Z30") (pintype "passive"))
      (node (ref "J5") (pin "Z32") (pinfunction "GND_Z32") (pintype "passive"))
      (node (ref "J5") (pin "Z4") (pinfunction "GND_Z4") (pintype "passive"))
      (node (ref "J5") (pin "Z6") (pinfunction "GND_Z6") (pintype "passive"))
      (node (ref "J5") (pin "Z8") (pinfunction "GND_Z8") (pintype "passive"))
    )
    (net (code "277") (name "unconnected-(J4C-HL-Pad0)") (class "Default")
      (node (ref "J4") (pin "0") (pinfunction "HL_0") (pintype "passive"))
    )
    (net (code "278") (name "unconnected-(J4D-+3.3V-PadD12)") (class "Default")
      (node (ref "J4") (pin "D12") (pinfunction "+3.3V_D12") (pintype "passive"))
    )
    (net (code "279") (name "unconnected-(J4D-+3.3V-PadD14)") (class "Default")
      (node (ref "J4") (pin "D14") (pinfunction "+3.3V_D14") (pintype "passive"))
    )
    (net (code "280") (name "unconnected-(J4D-+3.3V-PadD16)") (class "Default")
      (node (ref "J4") (pin "D16") (pinfunction "+3.3V_D16") (pintype "passive"))
    )
    (net (code "281") (name "unconnected-(J4D-+3.3V-PadD18)") (class "Default")
      (node (ref "J4") (pin "D18") (pinfunction "+3.3V_D18") (pintype "passive"))
    )
    (net (code "282") (name "unconnected-(J4D-+3.3V-PadD20)") (class "Default")
      (node (ref "J4") (pin "D20") (pinfunction "+3.3V_D20") (pintype "passive"))
    )
    (net (code "283") (name "unconnected-(J4D-+3.3V-PadD22)") (class "Default")
      (node (ref "J4") (pin "D22") (pinfunction "+3.3V_D22") (pintype "passive"))
    )
    (net (code "284") (name "unconnected-(J4D-+3.3V-PadD24)") (class "Default")
      (node (ref "J4") (pin "D24") (pinfunction "+3.3V_D24") (pintype "passive"))
    )
    (net (code "285") (name "unconnected-(J4D-+3.3V-PadD26)") (class "Default")
      (node (ref "J4") (pin "D26") (pinfunction "+3.3V_D26") (pintype "passive"))
    )
    (net (code "286") (name "unconnected-(J4D-+3.3V-PadD28)") (class "Default")
      (node (ref "J4") (pin "D28") (pinfunction "+3.3V_D28") (pintype "passive"))
    )
    (net (code "287") (name "unconnected-(J4D-+3.3V-PadD30)") (class "Default")
      (node (ref "J4") (pin "D30") (pinfunction "+3.3V_D30") (pintype "passive"))
    )
    (net (code "288") (name "unconnected-(J4D-RsvU-PadD5)") (class "Default")
      (node (ref "J4") (pin "D5") (pinfunction "RsvU_D5") (pintype "passive"))
    )
    (net (code "289") (name "unconnected-(J4D-RsvU-PadD8)") (class "Default")
      (node (ref "J4") (pin "D8") (pinfunction "RsvU_D8") (pintype "passive"))
    )
    (net (code "290") (name "unconnected-(J5D-Reserved-PadD16)") (class "Default")
      (node (ref "J5") (pin "D16") (pinfunction "Reserved_D16") (pintype "passive"))
    )
    (net (code "291") (name "unconnected-(J5D-Reserved-PadD18)") (class "Default")
      (node (ref "J5") (pin "D18") (pinfunction "Reserved_D18") (pintype "passive"))
    )
    (net (code "292") (name "unconnected-(J5D-Reserved-PadD20)") (class "Default")
      (node (ref "J5") (pin "D20") (pinfunction "Reserved_D20") (pintype "passive"))
    )
    (net (code "293") (name "unconnected-(J5D-Reserved-PadD22)") (class "Default")
      (node (ref "J5") (pin "D22") (pinfunction "Reserved_D22") (pintype "passive"))
    )
    (net (code "294") (name "unconnected-(J5D-Reserved-PadD24)") (class "Default")
      (node (ref "J5") (pin "D24") (pinfunction "Reserved_D24") (pintype "passive"))
    )
    (net (code "295") (name "unconnected-(J5D-Reserved-PadD26)") (class "Default")
      (node (ref "J5") (pin "D26") (pinfunction "Reserved_D26") (pintype "passive"))
    )
    (net (code "296") (name "unconnected-(J5D-Reserved-PadD28)") (class "Default")
      (node (ref "J5") (pin "D28") (pinfunction "Reserved_D28") (pintype "passive"))
    )
  )
)
